# lcd.net
KiCad netlist of a schematic drawn in Altium Designer
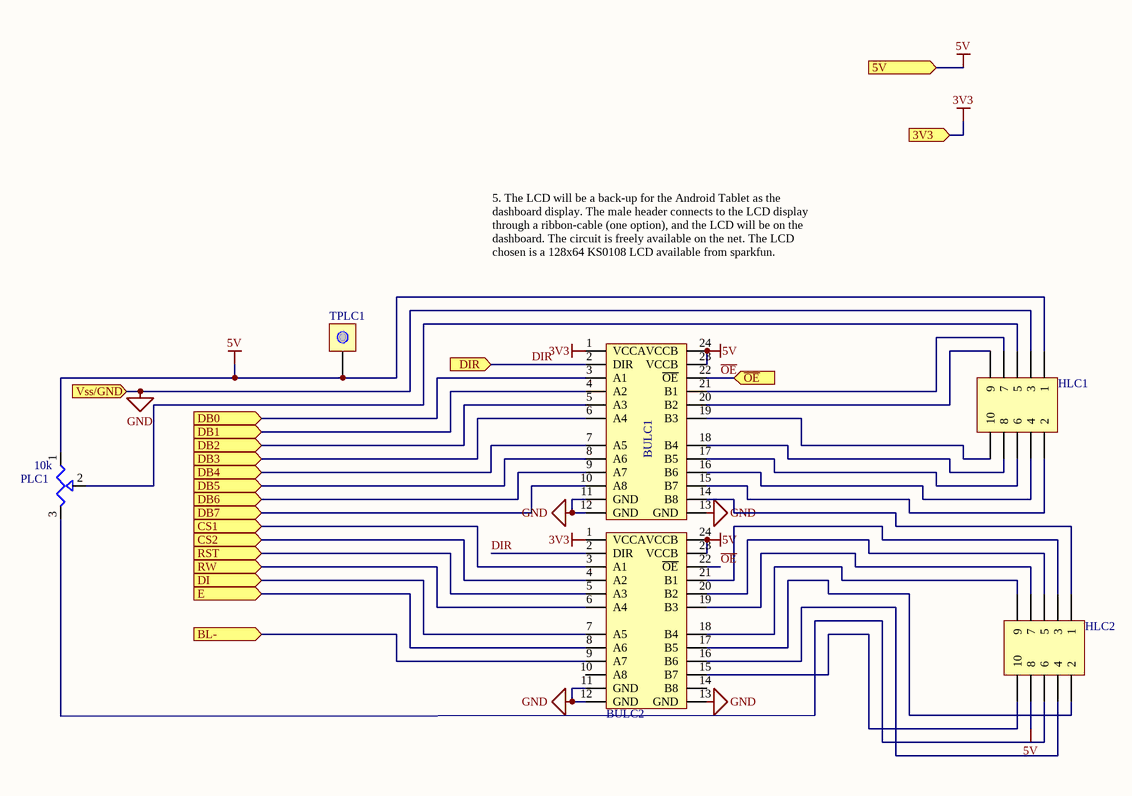
[diagram p0: lcd.SchDoc]

(export (version "E")
  (design (tool "Eeschema 10.0.6"))
  (components
    (comp (ref "BULC1")
      (value "BUS TRANSCEIVER")
      (footprint "TSSOP24")
      (description "8-BIT DUAL-SUPPLY BUS TRANSCEIVER WITH CONFIGURABLE VOLTAGE TRANSLATION AND 3-STATE OUTPUTS")
      (libsource (lib "add-schematic-library") (part "SN74LVC8T245"))
    )
    (comp (ref "BULC2")
      (value "BUS TRANSCEIVER")
      (footprint "TSSOP24")
      (description "8-BIT DUAL-SUPPLY BUS TRANSCEIVER WITH CONFIGURABLE VOLTAGE TRANSLATION AND 3-STATE OUTPUTS")
      (libsource (lib "add-schematic-library") (part "SN74LVC8T245"))
    )
    (comp (ref "HLC1")
      (value "Header 5X2H")
      (footprint "HDR2X5H")
      (description "Header, 5-Pin, Dual row, Right Angle")
      (fields (field (name "PUBLISHER") "Altium Limited"))
      (libsource (lib "Miscellaneous Connectors") (part "Header 5X2H"))
    )
    (comp (ref "HLC2")
      (value "Header 5X2H")
      (footprint "HDR2X5H")
      (description "Header, 5-Pin, Dual row, Right Angle")
      (fields (field (name "PUBLISHER") "Altium Limited"))
      (libsource (lib "Miscellaneous Connectors") (part "Header 5X2H"))
    )
    (comp (ref "PLC1")
      (value "10k")
      (footprint "TC33")
      (description "3mm SMD Trimming Pot")
      (fields (field (name "MANUFACTURER") "Bourns") (field (name "Comment") "Trimmer"))
      (libsource (lib "add-integrated-library") (part "TC33"))
    )
    (comp (ref "TPLC1")
      (value "TEST")
      (footprint "TESTPOINT")
      (description "TEST POINT")
      (libsource (lib "Miscellaneous") (part "TEST"))
    )
  )
  (nets
    (net (code "1") (name "/BL-") (class "Default")
      (node (ref "BULC2") (pin "9") (pinfunction "A7_9") (pintype "passive"))
    )
    (net (code "2") (name "/CS1") (class "Default")
      (node (ref "BULC2") (pin "3") (pinfunction "A1_3") (pintype "passive"))
    )
    (net (code "3") (name "/CS2") (class "Default")
      (node (ref "BULC2") (pin "4") (pinfunction "A2_4") (pintype "passive"))
    )
    (net (code "4") (name "/DB0") (class "Default")
      (node (ref "BULC1") (pin "3") (pinfunction "A1_3") (pintype "passive"))
    )
    (net (code "5") (name "/DB1") (class "Default")
      (node (ref "BULC1") (pin "4") (pinfunction "A2_4") (pintype "passive"))
    )
    (net (code "6") (name "/DB2") (class "Default")
      (node (ref "BULC1") (pin "5") (pinfunction "A3_5") (pintype "passive"))
    )
    (net (code "7") (name "/DB3") (class "Default")
      (node (ref "BULC1") (pin "6") (pinfunction "A4_6") (pintype "passive"))
    )
    (net (code "8") (name "/DB4") (class "Default")
      (node (ref "BULC1") (pin "7") (pinfunction "A5_7") (pintype "passive"))
    )
    (net (code "9") (name "/DB5") (class "Default")
      (node (ref "BULC1") (pin "8") (pinfunction "A6_8") (pintype "passive"))
    )
    (net (code "10") (name "/DB6") (class "Default")
      (node (ref "BULC1") (pin "9") (pinfunction "A7_9") (pintype "passive"))
    )
    (net (code "11") (name "/DB7") (class "Default")
      (node (ref "BULC1") (pin "10") (pinfunction "A8_10") (pintype "passive"))
    )
    (net (code "12") (name "/DI") (class "Default")
      (node (ref "BULC2") (pin "7") (pinfunction "A5_7") (pintype "passive"))
    )
    (net (code "13") (name "/DIR") (class "Default")
      (node (ref "BULC1") (pin "2") (pinfunction "DIR_2") (pintype "passive"))
      (node (ref "BULC2") (pin "2") (pinfunction "DIR_2") (pintype "passive"))
    )
    (net (code "14") (name "/E") (class "Default")
      (node (ref "BULC2") (pin "8") (pinfunction "A6_8") (pintype "passive"))
    )
    (net (code "15") (name "/RST") (class "Default")
      (node (ref "BULC2") (pin "5") (pinfunction "A3_5") (pintype "passive"))
    )
    (net (code "16") (name "/RW") (class "Default")
      (node (ref "BULC2") (pin "6") (pinfunction "A4_6") (pintype "passive"))
    )
    (net (code "17") (name "/~{OE}") (class "Default")
      (node (ref "BULC1") (pin "22") (pinfunction "~{OE}_22") (pintype "passive"))
      (node (ref "BULC2") (pin "22") (pinfunction "~{OE}_22") (pintype "passive"))
    )
    (net (code "18") (name "3V3") (class "Default")
      (node (ref "BULC1") (pin "1") (pinfunction "VCCA_1") (pintype "passive"))
      (node (ref "BULC2") (pin "1") (pinfunction "VCCA_1") (pintype "passive"))
    )
    (net (code "19") (name "5V") (class "Default")
      (node (ref "BULC1") (pin "23") (pinfunction "VCCB_23") (pintype "passive"))
      (node (ref "BULC1") (pin "24") (pinfunction "VCCB_24") (pintype "passive"))
      (node (ref "BULC2") (pin "23") (pinfunction "VCCB_23") (pintype "passive"))
      (node (ref "BULC2") (pin "24") (pinfunction "VCCB_24") (pintype "passive"))
      (node (ref "HLC1") (pin "1") (pinfunction "1_1") (pintype "passive"))
      (node (ref "HLC2") (pin "8") (pinfunction "8_8") (pintype "passive"))
      (node (ref "PLC1") (pin "1") (pinfunction "CCW_1") (pintype "passive"))
      (node (ref "TPLC1") (pin "0") (pinfunction "TP_0") (pintype "passive"))
    )
    (net (code "20") (name "GND") (class "Default")
      (node (ref "BULC1") (pin "11") (pinfunction "GND_11") (pintype "passive"))
      (node (ref "BULC1") (pin "12") (pinfunction "GND_12") (pintype "passive"))
      (node (ref "BULC1") (pin "13") (pinfunction "GND_13") (pintype "passive"))
      (node (ref "BULC2") (pin "11") (pinfunction "GND_11") (pintype "passive"))
      (node (ref "BULC2") (pin "12") (pinfunction "GND_12") (pintype "passive"))
      (node (ref "BULC2") (pin "13") (pinfunction "GND_13") (pintype "passive"))
      (node (ref "HLC1") (pin "3") (pinfunction "3_3") (pintype "passive"))
    )
    (net (code "21") (name "Net-(BULC1-B1)") (class "Default")
      (node (ref "BULC1") (pin "21") (pinfunction "B1_21") (pintype "passive"))
      (node (ref "HLC1") (pin "7") (pinfunction "7_7") (pintype "passive"))
    )
    (net (code "22") (name "Net-(BULC1-B2)") (class "Default")
      (node (ref "BULC1") (pin "20") (pinfunction "B2_20") (pintype "passive"))
      (node (ref "HLC1") (pin "9") (pinfunction "9_9") (pintype "passive"))
    )
    (net (code "23") (name "Net-(BULC1-B3)") (class "Default")
      (node (ref "BULC1") (pin "19") (pinfunction "B3_19") (pintype "passive"))
      (node (ref "HLC1") (pin "10") (pinfunction "10_10") (pintype "passive"))
    )
    (net (code "24") (name "Net-(BULC1-B4)") (class "Default")
      (node (ref "BULC1") (pin "18") (pinfunction "B4_18") (pintype "passive"))
      (node (ref "HLC1") (pin "8") (pinfunction "8_8") (pintype "passive"))
    )
    (net (code "25") (name "Net-(BULC1-B5)") (class "Default")
      (node (ref "BULC1") (pin "17") (pinfunction "B5_17") (pintype "passive"))
      (node (ref "HLC1") (pin "6") (pinfunction "6_6") (pintype "passive"))
    )
    (net (code "26") (name "Net-(BULC1-B6)") (class "Default")
      (node (ref "BULC1") (pin "16") (pinfunction "B6_16") (pintype "passive"))
      (node (ref "HLC1") (pin "4") (pinfunction "4_4") (pintype "passive"))
    )
    (net (code "27") (name "Net-(BULC1-B7)") (class "Default")
      (node (ref "BULC1") (pin "15") (pinfunction "B7_15") (pintype "passive"))
      (node (ref "HLC1") (pin "2") (pinfunction "2_2") (pintype "passive"))
    )
    (net (code "28") (name "Net-(BULC1-B8)") (class "Default")
      (node (ref "BULC1") (pin "14") (pinfunction "B8_14") (pintype "passive"))
      (node (ref "HLC2") (pin "1") (pinfunction "1_1") (pintype "passive"))
    )
    (net (code "29") (name "Net-(BULC2-B1)") (class "Default")
      (node (ref "BULC2") (pin "21") (pinfunction "B1_21") (pintype "passive"))
      (node (ref "HLC2") (pin "3") (pinfunction "3_3") (pintype "passive"))
    )
    (net (code "30") (name "Net-(BULC2-B2)") (class "Default")
      (node (ref "BULC2") (pin "20") (pinfunction "B2_20") (pintype "passive"))
      (node (ref "HLC2") (pin "5") (pinfunction "5_5") (pintype "passive"))
    )
    (net (code "31") (name "Net-(BULC2-B3)") (class "Default")
      (node (ref "BULC2") (pin "19") (pinfunction "B3_19") (pintype "passive"))
      (node (ref "HLC2") (pin "7") (pinfunction "7_7") (pintype "passive"))
    )
    (net (code "32") (name "Net-(BULC2-B4)") (class "Default")
      (node (ref "BULC2") (pin "18") (pinfunction "B4_18") (pintype "passive"))
      (node (ref "HLC2") (pin "9") (pinfunction "9_9") (pintype "passive"))
    )
    (net (code "33") (name "Net-(BULC2-B5)") (class "Default")
      (node (ref "BULC2") (pin "17") (pinfunction "B5_17") (pintype "passive"))
      (node (ref "HLC2") (pin "2") (pinfunction "2_2") (pintype "passive"))
    )
    (net (code "34") (name "Net-(BULC2-B6)") (class "Default")
      (node (ref "BULC2") (pin "16") (pinfunction "B6_16") (pintype "passive"))
      (node (ref "HLC2") (pin "4") (pinfunction "4_4") (pintype "passive"))
    )
    (net (code "35") (name "Net-(BULC2-B7)") (class "Default")
      (node (ref "BULC2") (pin "15") (pinfunction "B7_15") (pintype "passive"))
      (node (ref "HLC2") (pin "10") (pinfunction "10_10") (pintype "passive"))
    )
    (net (code "36") (name "Net-(PLC1-CW)") (class "Default")
      (node (ref "HLC2") (pin "6") (pinfunction "6_6") (pintype "passive"))
      (node (ref "PLC1") (pin "3") (pinfunction "CW_3") (pintype "passive"))
    )
    (net (code "37") (name "Net-(PLC1-WIPER)") (class "Default")
      (node (ref "HLC1") (pin "5") (pinfunction "5_5") (pintype "passive"))
      (node (ref "PLC1") (pin "2") (pinfunction "WIPER_2") (pintype "passive"))
    )
    (net (code "38") (name "unconnected-(BULC2-A8-Pad10)") (class "Default")
      (node (ref "BULC2") (pin "10") (pinfunction "A8_10") (pintype "passive"))
    )
    (net (code "39") (name "unconnected-(BULC2-B8-Pad14)") (class "Default")
      (node (ref "BULC2") (pin "14") (pinfunction "B8_14") (pintype "passive"))
    )
  )
)
